# DC_Motor_Control_2.net
KiCad netlist of a schematic drawn in Altium Designer
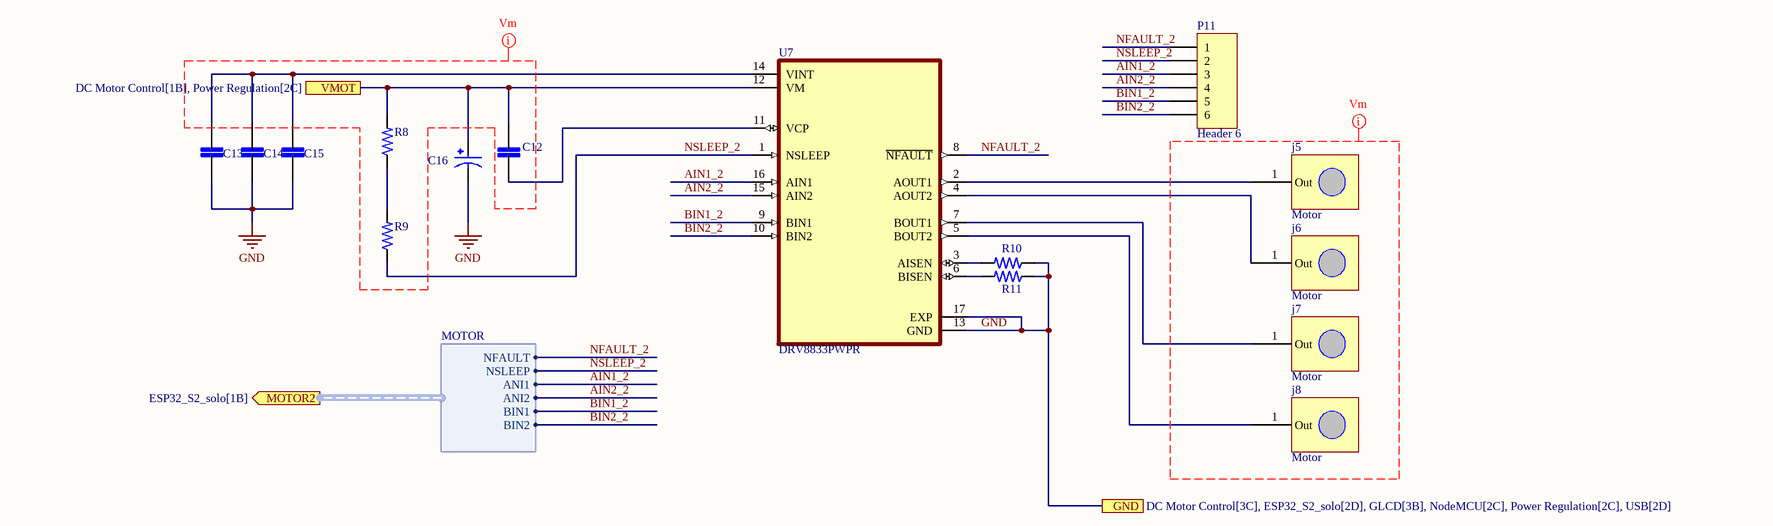
[diagram p0: DC Motor Control_2.SchDoc]

(export (version "E")
  (design (tool "Eeschema 10.0.6"))
  (components
    (comp (ref "C12")
      (value "LD051A121KAB2A")
      (footprint "CAPC2012X140N")
      (description "120PF 100V 10% 0805")
      (fields (field (name "MF") "{'manufacturer': u'AVX'}"))
      (libsource (lib "SnapEDA_Library") (part "LD051A121KAB2A"))
    )
    (comp (ref "C13")
      (value "LD051A121KAB2A")
      (footprint "CAPC2012X140N")
      (description "120PF 100V 10% 0805")
      (fields (field (name "MF") "{'manufacturer': u'AVX'}"))
      (libsource (lib "SnapEDA_Library") (part "LD051A121KAB2A"))
    )
    (comp (ref "C14")
      (value "LD051A121KAB2A")
      (footprint "CAPC2012X140N")
      (description "120PF 100V 10% 0805")
      (fields (field (name "MF") "{'manufacturer': u'AVX'}"))
      (libsource (lib "SnapEDA_Library") (part "LD051A121KAB2A"))
    )
    (comp (ref "C15")
      (value "LD051A121KAB2A")
      (footprint "CAPC2012X140N")
      (description "120PF 100V 10% 0805")
      (fields (field (name "MF") "{'manufacturer': u'AVX'}"))
      (libsource (lib "SnapEDA_Library") (part "LD051A121KAB2A"))
    )
    (comp (ref "C16")
      (value "EEEHA1V101UP")
      (footprint "CAP_EEEHA1V101UP")
      (fields (field (name "MF") "{'manufacturer': u'Panasonic'}"))
      (libsource (lib "SnapEDA_Library") (part "EEEHA1V101UP"))
    )
    (comp (ref "j5") (value "Motor") (footprint "Motor_pin") (libsource (lib "Schlib2") (part "Motor")))
    (comp (ref "j6") (value "Motor") (footprint "Motor_pin") (libsource (lib "Schlib2") (part "Motor")))
    (comp (ref "j7") (value "Motor") (footprint "Motor_pin") (libsource (lib "Schlib2") (part "Motor")))
    (comp (ref "j8") (value "Motor") (footprint "Motor_pin") (libsource (lib "Schlib2") (part "Motor")))
    (comp (ref "P11")
      (value "Header 6")
      (footprint "HDR1X6")
      (description "Header, 6-Pin")
      (fields (field (name "PUBLISHER") "Altium Limited"))
      (libsource (lib "Miscellaneous Connectors") (part "Header 6"))
    )
    (comp (ref "R8")
      (value "1-1879462-4")
      (footprint "RESC3115X65N")
      (description "RL73H 2B R43 1% 5K RL")
      (fields (field (name "MF") "{'manufacturer': u'TE Connectivity'}"))
      (libsource (lib "SnapEDA_Library") (part "1-1879462-4"))
    )
    (comp (ref "R9")
      (value "1-1879462-4")
      (footprint "RESC3115X65N")
      (description "RL73H 2B R43 1% 5K RL")
      (fields (field (name "MF") "{'manufacturer': u'TE Connectivity'}"))
      (libsource (lib "SnapEDA_Library") (part "1-1879462-4"))
    )
    (comp (ref "R10")
      (value "1-1879462-4")
      (footprint "RESC3115X65N")
      (description "RL73H 2B R43 1% 5K RL")
      (fields (field (name "MF") "{'manufacturer': u'TE Connectivity'}"))
      (libsource (lib "SnapEDA_Library") (part "1-1879462-4"))
    )
    (comp (ref "R11")
      (value "1-1879462-4")
      (footprint "RESC3115X65N")
      (description "RL73H 2B R43 1% 5K RL")
      (fields (field (name "MF") "{'manufacturer': u'TE Connectivity'}"))
      (libsource (lib "SnapEDA_Library") (part "1-1879462-4"))
    )
    (comp (ref "U7")
      (value "DRV8833PWPR")
      (footprint "IC_DRV8833PWPR")
      (description "10.8-V, 2-A dual H-bridge motor driver with current regulation 16-HTSSOP -40 to 85")
      (fields (field (name "MF") "{'manufacturer': u'Texas Instruments'}"))
      (libsource (lib "SnapEDA_Library") (part "DRV8833PWPR"))
    )
  )
  (nets
    (net (code "2") (name "/AIN1_2") (class "Default")
      (node (ref "P11") (pin "3") (pinfunction "3_3") (pintype "passive"))
      (node (ref "U7") (pin "16") (pinfunction "AIN1_16") (pintype "input"))
    )
    (net (code "3") (name "/AIN2_2") (class "Default")
      (node (ref "P11") (pin "4") (pinfunction "4_4") (pintype "passive"))
      (node (ref "U7") (pin "15") (pinfunction "AIN2_15") (pintype "input"))
    )
    (net (code "4") (name "/BIN1_2") (class "Default")
      (node (ref "P11") (pin "5") (pinfunction "5_5") (pintype "passive"))
      (node (ref "U7") (pin "9") (pinfunction "BIN1_9") (pintype "input"))
    )
    (net (code "5") (name "/BIN2_2") (class "Default")
      (node (ref "P11") (pin "6") (pinfunction "6_6") (pintype "passive"))
      (node (ref "U7") (pin "10") (pinfunction "BIN2_10") (pintype "input"))
    )
    (net (code "6") (name "/NFAULT_2") (class "Default")
      (node (ref "P11") (pin "1") (pinfunction "1_1") (pintype "passive"))
      (node (ref "U7") (pin "8") (pinfunction "~{NFAULT}_8") (pintype "output"))
    )
    (net (code "7") (name "/NSLEEP_2") (class "Default")
      (node (ref "P11") (pin "2") (pinfunction "2_2") (pintype "passive"))
      (node (ref "R9") (pin "1") (pinfunction "1_1") (pintype "passive"))
      (node (ref "U7") (pin "1") (pinfunction "NSLEEP_1") (pintype "input"))
    )
    (net (code "8") (name "/VMOT") (class "Default")
      (node (ref "C12") (pin "1") (pinfunction "1_1") (pintype "passive"))
      (node (ref "C16") (pin "1") (pinfunction "1_1") (pintype "passive"))
      (node (ref "R8") (pin "2") (pinfunction "2_2") (pintype "passive"))
      (node (ref "U7") (pin "12") (pinfunction "VM_12") (pintype "power_in"))
    )
    (net (code "10") (name "GND") (class "Default")
      (node (ref "C13") (pin "2") (pinfunction "2_2") (pintype "passive"))
      (node (ref "C14") (pin "2") (pinfunction "2_2") (pintype "passive"))
      (node (ref "C15") (pin "2") (pinfunction "2_2") (pintype "passive"))
      (node (ref "C16") (pin "2") (pinfunction "2_2") (pintype "power_in"))
      (node (ref "R10") (pin "1") (pinfunction "1_1") (pintype "passive"))
      (node (ref "R11") (pin "1") (pinfunction "1_1") (pintype "passive"))
      (node (ref "U7") (pin "13") (pinfunction "GND_13") (pintype "power_in"))
      (node (ref "U7") (pin "17") (pinfunction "EXP_17") (pintype "passive"))
    )
    (net (code "11") (name "Net-(R8-Pad1)") (class "Default")
      (node (ref "R8") (pin "1") (pinfunction "1_1") (pintype "passive"))
      (node (ref "R9") (pin "2") (pinfunction "2_2") (pintype "passive"))
    )
    (net (code "12") (name "Net-(U7-AISEN)") (class "Default")
      (node (ref "R10") (pin "2") (pinfunction "2_2") (pintype "passive"))
      (node (ref "U7") (pin "3") (pinfunction "AISEN_3") (pintype "bidirectional"))
    )
    (net (code "13") (name "Net-(U7-AOUT1)") (class "Default")
      (node (ref "U7") (pin "2") (pinfunction "AOUT1_2") (pintype "output"))
      (node (ref "j5") (pin "1") (pinfunction "Out_1") (pintype "passive"))
    )
    (net (code "14") (name "Net-(U7-AOUT2)") (class "Default")
      (node (ref "U7") (pin "4") (pinfunction "AOUT2_4") (pintype "output"))
      (node (ref "j6") (pin "1") (pinfunction "Out_1") (pintype "passive"))
    )
    (net (code "15") (name "Net-(U7-BISEN)") (class "Default")
      (node (ref "R11") (pin "2") (pinfunction "2_2") (pintype "passive"))
      (node (ref "U7") (pin "6") (pinfunction "BISEN_6") (pintype "bidirectional"))
    )
    (net (code "16") (name "Net-(U7-BOUT1)") (class "Default")
      (node (ref "U7") (pin "7") (pinfunction "BOUT1_7") (pintype "output"))
      (node (ref "j7") (pin "1") (pinfunction "Out_1") (pintype "passive"))
    )
    (net (code "17") (name "Net-(U7-BOUT2)") (class "Default")
      (node (ref "U7") (pin "5") (pinfunction "BOUT2_5") (pintype "output"))
      (node (ref "j8") (pin "1") (pinfunction "Out_1") (pintype "passive"))
    )
    (net (code "18") (name "Net-(U7-VCP)") (class "Default")
      (node (ref "C12") (pin "2") (pinfunction "2_2") (pintype "passive"))
      (node (ref "U7") (pin "11") (pinfunction "VCP_11") (pintype "bidirectional"))
    )
    (net (code "19") (name "Net-(U7-VINT)") (class "Default")
      (node (ref "C13") (pin "1") (pinfunction "1_1") (pintype "passive"))
      (node (ref "C14") (pin "1") (pinfunction "1_1") (pintype "passive"))
      (node (ref "C15") (pin "1") (pinfunction "1_1") (pintype "passive"))
      (node (ref "U7") (pin "14") (pinfunction "VINT_14") (pintype "power_in"))
    )
  )
)
